# USB_Host.net
KiCad netlist of a schematic drawn in EAGLE
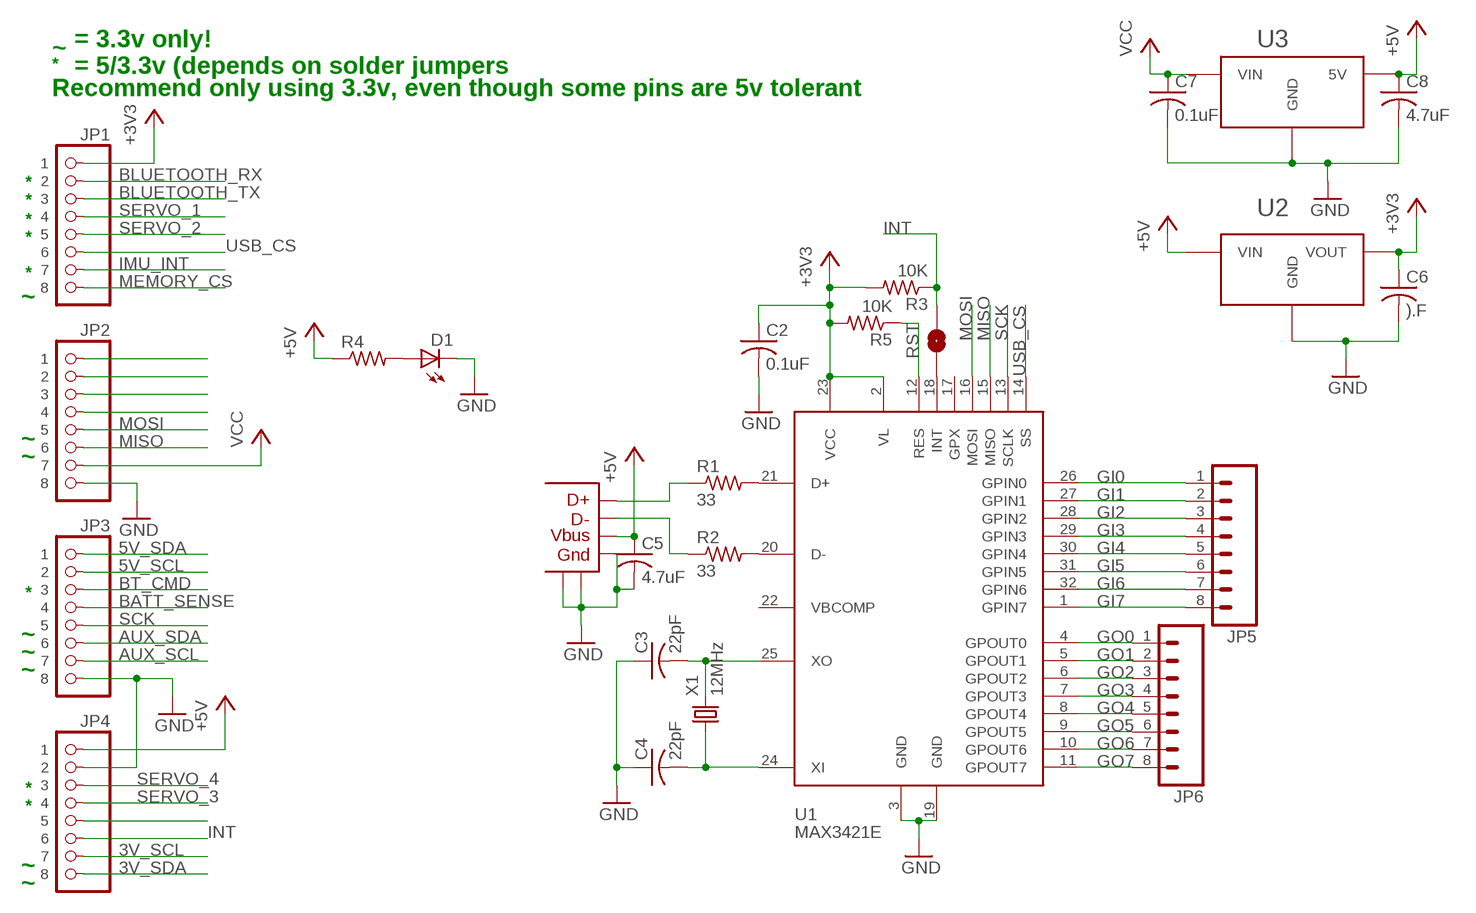
[diagram p0: schematic, sheet 1]

(export (version "E")
  (design (tool "Eeschema 10.0.6"))
  (components
    (comp (ref "C2")
      (value "0.1uF")
      (footprint "eagle-import:C0603")
      (libsource (lib "eagle-import") (part "C-USC0603"))
    )
    (comp (ref "C3")
      (value "22pF")
      (footprint "eagle-import:C0603")
      (libsource (lib "eagle-import") (part "C-USC0603"))
    )
    (comp (ref "C4")
      (value "22pF")
      (footprint "eagle-import:C0603")
      (libsource (lib "eagle-import") (part "C-USC0603"))
    )
    (comp (ref "C5")
      (value "4.7uF")
      (footprint "eagle-import:C0603")
      (libsource (lib "eagle-import") (part "C-USC0603"))
    )
    (comp (ref "C6")
      (value ").F")
      (footprint "eagle-import:C0603")
      (libsource (lib "eagle-import") (part "C-USC0603"))
    )
    (comp (ref "C7")
      (value "0.1uF")
      (footprint "eagle-import:C0603")
      (libsource (lib "eagle-import") (part "C-USC0603"))
    )
    (comp (ref "C8")
      (value "4.7uF")
      (footprint "eagle-import:C0603")
      (libsource (lib "eagle-import") (part "C-USC0603"))
    )
    (comp (ref "D1")
      (value "LED-GREENLED-0805_NO_SILK")
      (footprint "eagle-import:LED-0805")
      (libsource (lib "eagle-import") (part "LED-GREENLED-0805_NO_SILK"))
    )
    (comp (ref "JP1")
      (value "8-PIN_HEADER")
      (footprint "eagle-import:8-PIN_RECEPTACLE_LOCK_NO-SS")
      (libsource (lib "eagle-import") (part "8-PIN_HEADER"))
    )
    (comp (ref "JP2")
      (value "8-PIN_HEADER")
      (footprint "eagle-import:8-PIN_RECEPTACLE_LOCK_NO-SS")
      (libsource (lib "eagle-import") (part "8-PIN_HEADER"))
    )
    (comp (ref "JP3")
      (value "8-PIN_HEADER")
      (footprint "eagle-import:8-PIN_RECEPTACLE_LOCK_NO-SS")
      (libsource (lib "eagle-import") (part "8-PIN_HEADER"))
    )
    (comp (ref "JP4")
      (value "8-PIN_HEADER")
      (footprint "eagle-import:8-PIN_RECEPTACLE_LOCK_NO-SS")
      (libsource (lib "eagle-import") (part "8-PIN_HEADER"))
    )
    (comp (ref "JP5")
      (value "M081X08")
      (footprint "eagle-import:1X08")
      (libsource (lib "eagle-import") (part "M081X08"))
    )
    (comp (ref "JP6")
      (value "M081X08")
      (footprint "eagle-import:1X08")
      (libsource (lib "eagle-import") (part "M081X08"))
    )
    (comp (ref "R1")
      (value "33")
      (footprint "eagle-import:R0603")
      (libsource (lib "eagle-import") (part "R-US_R0603"))
    )
    (comp (ref "R2")
      (value "33")
      (footprint "eagle-import:R0603")
      (libsource (lib "eagle-import") (part "R-US_R0603"))
    )
    (comp (ref "R3")
      (value "10K")
      (footprint "eagle-import:R0603")
      (libsource (lib "eagle-import") (part "R-US_R0603"))
    )
    (comp (ref "R4")
      (value "R-US_R0603")
      (footprint "eagle-import:R0603")
      (libsource (lib "eagle-import") (part "R-US_R0603"))
    )
    (comp (ref "R5")
      (value "10K")
      (footprint "eagle-import:R0603")
      (libsource (lib "eagle-import") (part "R-US_R0603"))
    )
    (comp (ref "SJ1")
      (value "SOLDERJUMPERTRACE")
      (footprint "eagle-import:SJ_2S-TRACE")
      (libsource (lib "eagle-import") (part "SOLDERJUMPERTRACE"))
    )
    (comp (ref "U$1")
      (value "USB_SOCKETTYPE-A")
      (footprint "eagle-import:USB_SOCKET")
      (fields (field (name "PART#") "USB-A1HSW6"))
      (libsource (lib "eagle-import") (part "USB_SOCKETTYPE-A"))
    )
    (comp (ref "U1")
      (value "MAX3421E")
      (footprint "eagle-import:TQFP32_8MIL")
      (libsource (lib "eagle-import") (part "MAX3421E"))
    )
    (comp (ref "U2")
      (value "AP7313SOT23R")
      (footprint "eagle-import:SOT23")
      (libsource (lib "eagle-import") (part "AP7313SOT23R"))
    )
    (comp (ref "U3")
      (value "LM2931")
      (footprint "eagle-import:TO263")
      (libsource (lib "eagle-import") (part "LM2931"))
    )
    (comp (ref "X1")
      (value "12MHz")
      (footprint "eagle-import:CRYSTAL-TXC-7A")
      (fields (field (name "PART#") "7A-12.000MAAE-T"))
      (libsource (lib "eagle-import") (part "CRYSTALTXC-7A"))
    )
  )
  (nets
    (net (code "1") (name "+3V3") (class "Default")
      (node (ref "C2") (pin "1") (pinfunction "1_1") (pintype "passive"))
      (node (ref "C6") (pin "1") (pinfunction "1_1") (pintype "passive"))
      (node (ref "JP1") (pin "P$1") (pinfunction "1_P$1") (pintype "passive"))
      (node (ref "R3") (pin "2") (pinfunction "2_2") (pintype "passive"))
      (node (ref "R5") (pin "2") (pinfunction "2_2") (pintype "passive"))
      (node (ref "U1") (pin "2") (pinfunction "VL_2") (pintype "input"))
      (node (ref "U1") (pin "23") (pinfunction "VCC_23") (pintype "power_in"))
      (node (ref "U2") (pin "P$2") (pinfunction "VOUT_P$2") (pintype "bidirectional"))
    )
    (net (code "2") (name "+5V") (class "Default")
      (node (ref "C5") (pin "1") (pinfunction "1_1") (pintype "passive"))
      (node (ref "C8") (pin "1") (pinfunction "1_1") (pintype "passive"))
      (node (ref "JP4") (pin "P$1") (pinfunction "1_P$1") (pintype "passive"))
      (node (ref "R4") (pin "1") (pinfunction "1_1") (pintype "passive"))
      (node (ref "U$1") (pin "P$1") (pinfunction "VBUS_P$1") (pintype "bidirectional"))
      (node (ref "U2") (pin "P$3") (pinfunction "VIN_P$3") (pintype "bidirectional"))
      (node (ref "U3") (pin "P$3") (pinfunction "5V_P$3") (pintype "bidirectional"))
    )
    (net (code "3") (name "/3V_SCL") (class "Default")
      (node (ref "JP4") (pin "P$7") (pinfunction "7_P$7") (pintype "passive"))
    )
    (net (code "4") (name "/3V_SDA") (class "Default")
      (node (ref "JP4") (pin "P$8") (pinfunction "8_P$8") (pintype "passive"))
    )
    (net (code "5") (name "/5V_SCL") (class "Default")
      (node (ref "JP3") (pin "P$2") (pinfunction "2_P$2") (pintype "passive"))
    )
    (net (code "6") (name "/5V_SDA") (class "Default")
      (node (ref "JP3") (pin "P$1") (pinfunction "1_P$1") (pintype "passive"))
    )
    (net (code "7") (name "/AUX_SCL") (class "Default")
      (node (ref "JP3") (pin "P$7") (pinfunction "7_P$7") (pintype "passive"))
    )
    (net (code "8") (name "/AUX_SDA") (class "Default")
      (node (ref "JP3") (pin "P$6") (pinfunction "6_P$6") (pintype "passive"))
    )
    (net (code "9") (name "/BATT_SENSE") (class "Default")
      (node (ref "JP3") (pin "P$4") (pinfunction "4_P$4") (pintype "passive"))
    )
    (net (code "10") (name "/BLUETOOTH_RX") (class "Default")
      (node (ref "JP1") (pin "P$2") (pinfunction "2_P$2") (pintype "passive"))
    )
    (net (code "11") (name "/BLUETOOTH_TX") (class "Default")
      (node (ref "JP1") (pin "P$3") (pinfunction "3_P$3") (pintype "passive"))
    )
    (net (code "12") (name "/BT_CMD") (class "Default")
      (node (ref "JP3") (pin "P$3") (pinfunction "3_P$3") (pintype "passive"))
    )
    (net (code "13") (name "/GI0") (class "Default")
      (node (ref "JP5") (pin "1") (pinfunction "1_1") (pintype "passive"))
      (node (ref "U1") (pin "26") (pinfunction "GPIN0_26") (pintype "input"))
    )
    (net (code "14") (name "/GI1") (class "Default")
      (node (ref "JP5") (pin "2") (pinfunction "2_2") (pintype "passive"))
      (node (ref "U1") (pin "27") (pinfunction "GPIN1_27") (pintype "input"))
    )
    (net (code "15") (name "/GI2") (class "Default")
      (node (ref "JP5") (pin "3") (pinfunction "3_3") (pintype "passive"))
      (node (ref "U1") (pin "28") (pinfunction "GPIN2_28") (pintype "input"))
    )
    (net (code "16") (name "/GI3") (class "Default")
      (node (ref "JP5") (pin "4") (pinfunction "4_4") (pintype "passive"))
      (node (ref "U1") (pin "29") (pinfunction "GPIN3_29") (pintype "input"))
    )
    (net (code "17") (name "/GI4") (class "Default")
      (node (ref "JP5") (pin "5") (pinfunction "5_5") (pintype "passive"))
      (node (ref "U1") (pin "30") (pinfunction "GPIN4_30") (pintype "input"))
    )
    (net (code "18") (name "/GI5") (class "Default")
      (node (ref "JP5") (pin "6") (pinfunction "6_6") (pintype "passive"))
      (node (ref "U1") (pin "31") (pinfunction "GPIN5_31") (pintype "input"))
    )
    (net (code "19") (name "/GI6") (class "Default")
      (node (ref "JP5") (pin "7") (pinfunction "7_7") (pintype "passive"))
      (node (ref "U1") (pin "32") (pinfunction "GPIN6_32") (pintype "input"))
    )
    (net (code "20") (name "/GI7") (class "Default")
      (node (ref "JP5") (pin "8") (pinfunction "8_8") (pintype "passive"))
      (node (ref "U1") (pin "1") (pinfunction "GPIN7_1") (pintype "input"))
    )
    (net (code "21") (name "/GO0") (class "Default")
      (node (ref "JP6") (pin "1") (pinfunction "1_1") (pintype "passive"))
      (node (ref "U1") (pin "4") (pinfunction "GPOUT0_4") (pintype "output"))
    )
    (net (code "22") (name "/GO1") (class "Default")
      (node (ref "JP6") (pin "2") (pinfunction "2_2") (pintype "passive"))
      (node (ref "U1") (pin "5") (pinfunction "GPOUT1_5") (pintype "output"))
    )
    (net (code "23") (name "/GO2") (class "Default")
      (node (ref "JP6") (pin "3") (pinfunction "3_3") (pintype "passive"))
      (node (ref "U1") (pin "6") (pinfunction "GPOUT2_6") (pintype "output"))
    )
    (net (code "24") (name "/GO3") (class "Default")
      (node (ref "JP6") (pin "4") (pinfunction "4_4") (pintype "passive"))
      (node (ref "U1") (pin "7") (pinfunction "GPOUT3_7") (pintype "output"))
    )
    (net (code "25") (name "/GO4") (class "Default")
      (node (ref "JP6") (pin "5") (pinfunction "5_5") (pintype "passive"))
      (node (ref "U1") (pin "8") (pinfunction "GPOUT4_8") (pintype "output"))
    )
    (net (code "26") (name "/GO5") (class "Default")
      (node (ref "JP6") (pin "6") (pinfunction "6_6") (pintype "passive"))
      (node (ref "U1") (pin "9") (pinfunction "GPOUT5_9") (pintype "output"))
    )
    (net (code "27") (name "/GO6") (class "Default")
      (node (ref "JP6") (pin "7") (pinfunction "7_7") (pintype "passive"))
      (node (ref "U1") (pin "10") (pinfunction "GPOUT6_10") (pintype "output"))
    )
    (net (code "28") (name "/GO7") (class "Default")
      (node (ref "JP6") (pin "8") (pinfunction "8_8") (pintype "passive"))
      (node (ref "U1") (pin "11") (pinfunction "GPOUT7_11") (pintype "output"))
    )
    (net (code "29") (name "/IMU_INT") (class "Default")
      (node (ref "JP1") (pin "P$7") (pinfunction "7_P$7") (pintype "passive"))
    )
    (net (code "30") (name "/INT") (class "Default")
      (node (ref "JP4") (pin "P$6") (pinfunction "6_P$6") (pintype "passive"))
      (node (ref "R3") (pin "1") (pinfunction "1_1") (pintype "passive"))
      (node (ref "SJ1") (pin "2") (pinfunction "2_2") (pintype "passive"))
    )
    (net (code "31") (name "/MEMORY_CS") (class "Default")
      (node (ref "JP1") (pin "P$8") (pinfunction "8_P$8") (pintype "passive"))
    )
    (net (code "32") (name "/MISO") (class "Default")
      (node (ref "JP2") (pin "P$6") (pinfunction "6_P$6") (pintype "passive"))
      (node (ref "U1") (pin "15") (pinfunction "MISO_15") (pintype "output"))
    )
    (net (code "33") (name "/MOSI") (class "Default")
      (node (ref "JP2") (pin "P$5") (pinfunction "5_P$5") (pintype "passive"))
      (node (ref "U1") (pin "16") (pinfunction "MOSI_16") (pintype "input"))
    )
    (net (code "34") (name "/RST") (class "Default")
      (node (ref "R5") (pin "1") (pinfunction "1_1") (pintype "passive"))
      (node (ref "U1") (pin "12") (pinfunction "RES_12") (pintype "input"))
    )
    (net (code "35") (name "/SCK") (class "Default")
      (node (ref "JP3") (pin "P$5") (pinfunction "5_P$5") (pintype "passive"))
      (node (ref "U1") (pin "13") (pinfunction "SCLK_13") (pintype "input"))
    )
    (net (code "36") (name "/SERVO_1") (class "Default")
      (node (ref "JP1") (pin "P$4") (pinfunction "4_P$4") (pintype "passive"))
    )
    (net (code "37") (name "/SERVO_2") (class "Default")
      (node (ref "JP1") (pin "P$5") (pinfunction "5_P$5") (pintype "passive"))
    )
    (net (code "38") (name "/SERVO_3") (class "Default")
      (node (ref "JP4") (pin "P$4") (pinfunction "4_P$4") (pintype "passive"))
    )
    (net (code "39") (name "/SERVO_4") (class "Default")
      (node (ref "JP4") (pin "P$3") (pinfunction "3_P$3") (pintype "passive"))
    )
    (net (code "40") (name "/USB_CS") (class "Default")
      (node (ref "JP1") (pin "P$6") (pinfunction "6_P$6") (pintype "passive"))
      (node (ref "U1") (pin "14") (pinfunction "SS_14") (pintype "input"))
    )
    (net (code "41") (name "GND") (class "Default")
      (node (ref "C2") (pin "2") (pinfunction "2_2") (pintype "passive"))
      (node (ref "C3") (pin "1") (pinfunction "1_1") (pintype "passive"))
      (node (ref "C4") (pin "1") (pinfunction "1_1") (pintype "passive"))
      (node (ref "C5") (pin "2") (pinfunction "2_2") (pintype "passive"))
      (node (ref "C6") (pin "2") (pinfunction "2_2") (pintype "passive"))
      (node (ref "C7") (pin "2") (pinfunction "2_2") (pintype "passive"))
      (node (ref "C8") (pin "2") (pinfunction "2_2") (pintype "passive"))
      (node (ref "D1") (pin "2") (pinfunction "C_2") (pintype "passive"))
      (node (ref "JP2") (pin "P$8") (pinfunction "8_P$8") (pintype "passive"))
      (node (ref "JP3") (pin "P$8") (pinfunction "8_P$8") (pintype "passive"))
      (node (ref "JP4") (pin "P$2") (pinfunction "2_P$2") (pintype "passive"))
      (node (ref "U$1") (pin "P$4") (pinfunction "GND_P$4") (pintype "bidirectional"))
      (node (ref "U$1") (pin "P$5") (pinfunction "P$1_P$5") (pintype "bidirectional"))
      (node (ref "U$1") (pin "P$6") (pinfunction "P$2_P$6") (pintype "bidirectional"))
      (node (ref "U1") (pin "19") (pinfunction "GND_19") (pintype "power_in"))
      (node (ref "U1") (pin "3") (pinfunction "GND_3") (pintype "power_in"))
      (node (ref "U2") (pin "P$1") (pinfunction "GND_P$1") (pintype "bidirectional"))
      (node (ref "U3") (pin "P$1") (pinfunction "GND_P$1") (pintype "bidirectional"))
    )
    (net (code "42") (name "Net-(D1-A)") (class "Default")
      (node (ref "D1") (pin "1") (pinfunction "A_1") (pintype "passive"))
      (node (ref "R4") (pin "2") (pinfunction "2_2") (pintype "passive"))
    )
    (net (code "43") (name "Net-(U$1-D+)") (class "Default")
      (node (ref "R1") (pin "1") (pinfunction "1_1") (pintype "passive"))
      (node (ref "U$1") (pin "P$3") (pinfunction "D+_P$3") (pintype "bidirectional"))
    )
    (net (code "44") (name "Net-(U$1-D-)") (class "Default")
      (node (ref "R2") (pin "1") (pinfunction "1_1") (pintype "passive"))
      (node (ref "U$1") (pin "P$2") (pinfunction "D-_P$2") (pintype "bidirectional"))
    )
    (net (code "45") (name "Net-(U1-D+)") (class "Default")
      (node (ref "R1") (pin "2") (pinfunction "2_2") (pintype "passive"))
      (node (ref "U1") (pin "21") (pinfunction "D+_21") (pintype "bidirectional"))
    )
    (net (code "46") (name "Net-(U1-D-)") (class "Default")
      (node (ref "R2") (pin "2") (pinfunction "2_2") (pintype "passive"))
      (node (ref "U1") (pin "20") (pinfunction "D-_20") (pintype "bidirectional"))
    )
    (net (code "47") (name "Net-(U1-INT)") (class "Default")
      (node (ref "SJ1") (pin "1") (pinfunction "1_1") (pintype "passive"))
      (node (ref "U1") (pin "18") (pinfunction "INT_18") (pintype "output"))
    )
    (net (code "48") (name "Net-(U1-XI)") (class "Default")
      (node (ref "C4") (pin "2") (pinfunction "2_2") (pintype "passive"))
      (node (ref "U1") (pin "24") (pinfunction "XI_24") (pintype "input"))
      (node (ref "X1") (pin "P$1") (pinfunction "1_P$1") (pintype "passive"))
    )
    (net (code "49") (name "Net-(U1-XO)") (class "Default")
      (node (ref "C3") (pin "2") (pinfunction "2_2") (pintype "passive"))
      (node (ref "U1") (pin "25") (pinfunction "XO_25") (pintype "output"))
      (node (ref "X1") (pin "P$2") (pinfunction "2_P$2") (pintype "passive"))
    )
    (net (code "50") (name "VCC") (class "Default")
      (node (ref "C7") (pin "1") (pinfunction "1_1") (pintype "passive"))
      (node (ref "JP2") (pin "P$7") (pinfunction "7_P$7") (pintype "passive"))
      (node (ref "U3") (pin "P$2") (pinfunction "VIN_P$2") (pintype "bidirectional"))
    )
    (net (code "51") (name "unconnected-(JP2-1-PadP$1)") (class "Default")
      (node (ref "JP2") (pin "P$1") (pinfunction "1_P$1") (pintype "passive"))
    )
    (net (code "52") (name "unconnected-(JP2-2-PadP$2)") (class "Default")
      (node (ref "JP2") (pin "P$2") (pinfunction "2_P$2") (pintype "passive"))
    )
    (net (code "53") (name "unconnected-(JP2-3-PadP$3)") (class "Default")
      (node (ref "JP2") (pin "P$3") (pinfunction "3_P$3") (pintype "passive"))
    )
    (net (code "54") (name "unconnected-(JP2-4-PadP$4)") (class "Default")
      (node (ref "JP2") (pin "P$4") (pinfunction "4_P$4") (pintype "passive"))
    )
    (net (code "55") (name "unconnected-(JP4-5-PadP$5)") (class "Default")
      (node (ref "JP4") (pin "P$5") (pinfunction "5_P$5") (pintype "passive"))
    )
    (net (code "56") (name "unconnected-(U1-GPX-Pad17)") (class "Default")
      (node (ref "U1") (pin "17") (pinfunction "GPX_17") (pintype "output"))
    )
    (net (code "57") (name "unconnected-(U1-VBCOMP-Pad22)") (class "Default")
      (node (ref "U1") (pin "22") (pinfunction "VBCOMP_22") (pintype "input"))
    )
  )
)
